# WattMeter_v4_SPI_Nov19_2018.net
KiCad netlist of a schematic drawn in EAGLE
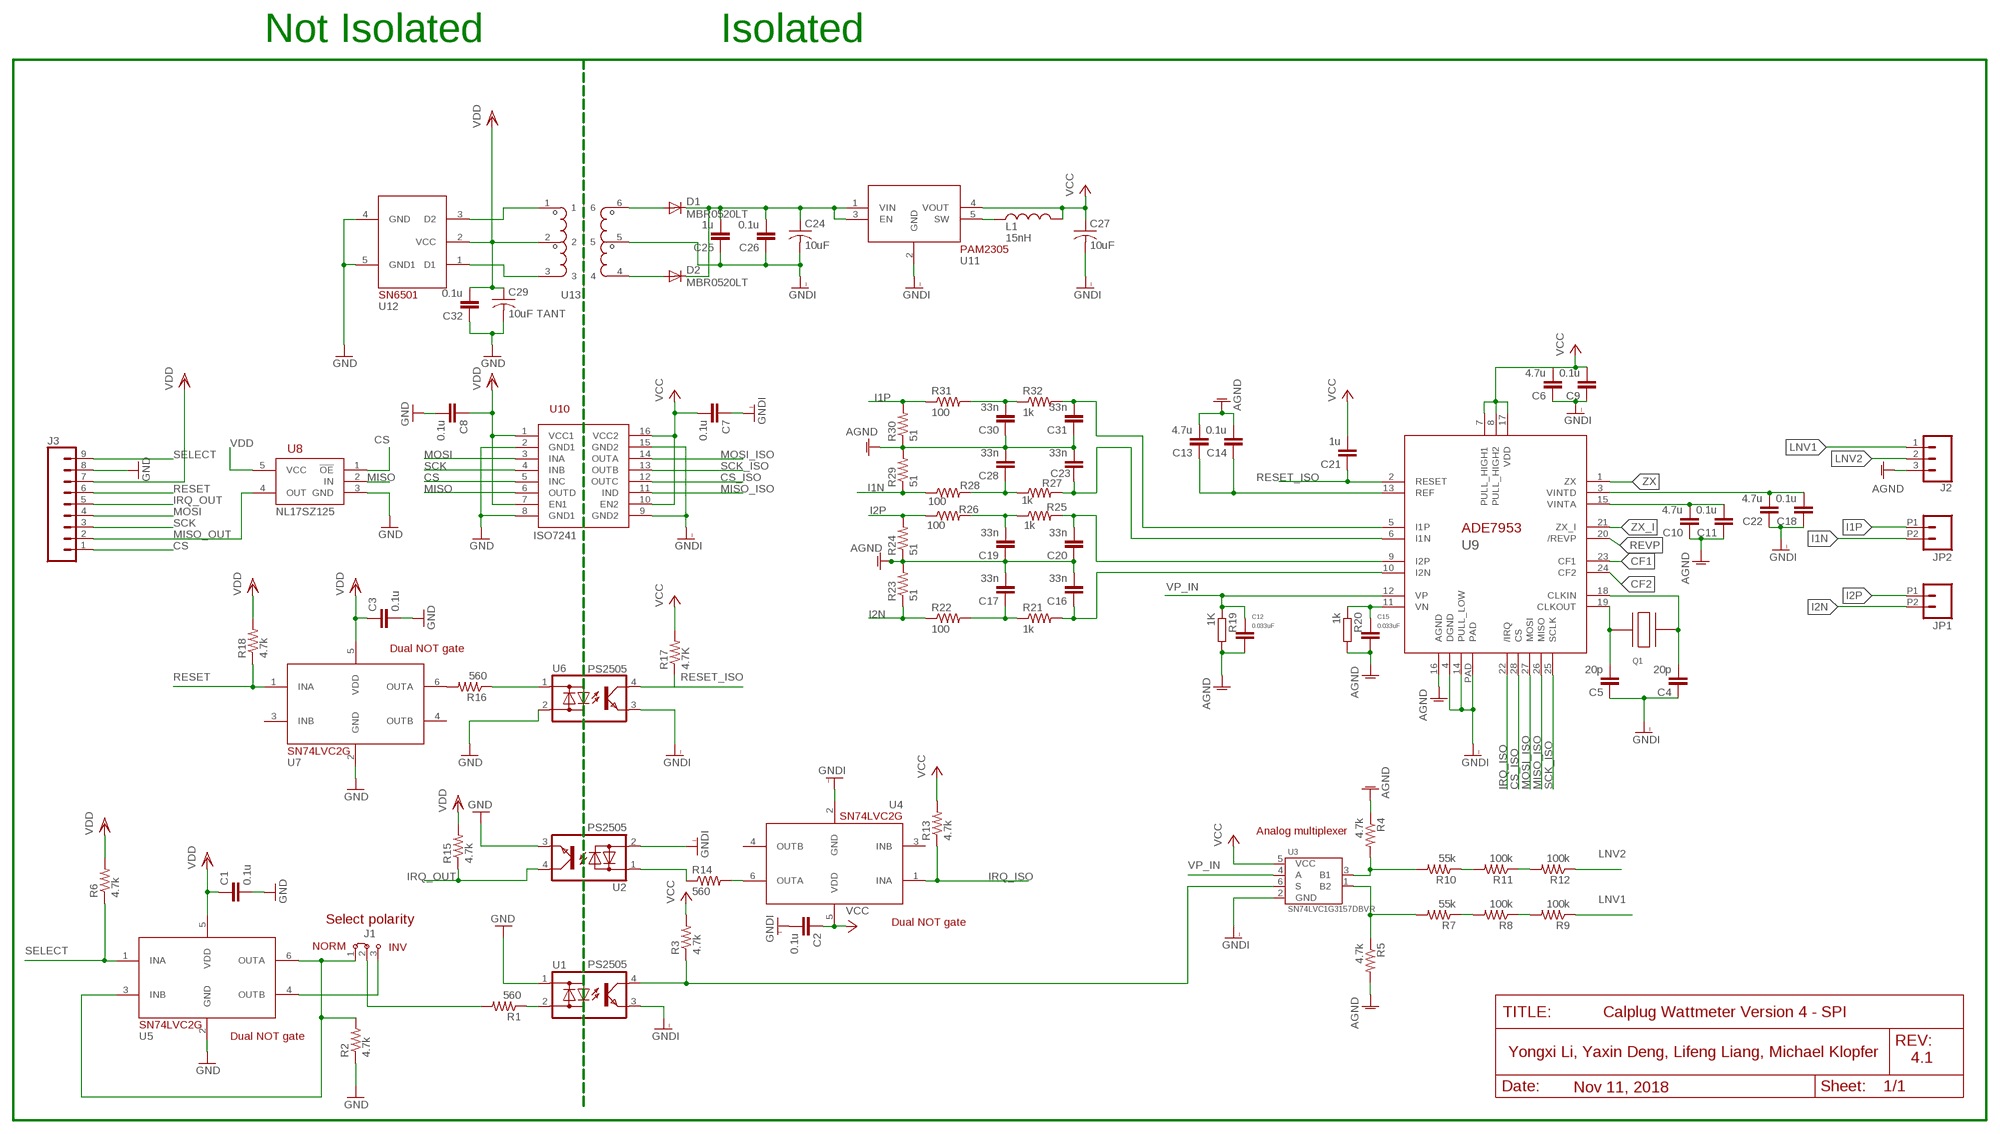
[diagram p0: schematic, sheet 1]

(export (version "E")
  (design (tool "Eeschema 10.0.6"))
  (components
    (comp (ref "C1")
      (value "0.1u")
      (footprint "eagle-import:0402-CAP")
      (libsource (lib "eagle-import") (part "0402-CAP"))
    )
    (comp (ref "C2")
      (value "0.1u")
      (footprint "eagle-import:0402-CAP")
      (libsource (lib "eagle-import") (part "0402-CAP"))
    )
    (comp (ref "C3")
      (value "0.1u")
      (footprint "eagle-import:0402-CAP")
      (libsource (lib "eagle-import") (part "0402-CAP"))
    )
    (comp (ref "C4")
      (value "20p")
      (footprint "eagle-import:0402-CAP")
      (libsource (lib "eagle-import") (part "0402-CAP"))
    )
    (comp (ref "C5")
      (value "20p")
      (footprint "eagle-import:0402-CAP")
      (libsource (lib "eagle-import") (part "0402-CAP"))
    )
    (comp (ref "C6")
      (value "4.7u")
      (footprint "eagle-import:0402-CAP")
      (libsource (lib "eagle-import") (part "0402-CAP"))
    )
    (comp (ref "C7")
      (value "0.1u")
      (footprint "eagle-import:0402-CAP")
      (libsource (lib "eagle-import") (part "0402-CAP"))
    )
    (comp (ref "C8")
      (value "0.1u")
      (footprint "eagle-import:0402-CAP")
      (libsource (lib "eagle-import") (part "0402-CAP"))
    )
    (comp (ref "C9")
      (value "0.1u")
      (footprint "eagle-import:0402-CAP")
      (libsource (lib "eagle-import") (part "0402-CAP"))
    )
    (comp (ref "C10")
      (value "4.7u")
      (footprint "eagle-import:0402-CAP")
      (libsource (lib "eagle-import") (part "0402-CAP"))
    )
    (comp (ref "C11")
      (value "0.1u")
      (footprint "eagle-import:0402-CAP")
      (libsource (lib "eagle-import") (part "0402-CAP"))
    )
    (comp (ref "C12")
      (value "0.033uF")
      (footprint "eagle-import:C0805K")
      (libsource (lib "eagle-import") (part "C-EUC0805K"))
    )
    (comp (ref "C13")
      (value "4.7u")
      (footprint "eagle-import:0402-CAP")
      (libsource (lib "eagle-import") (part "0402-CAP"))
    )
    (comp (ref "C14")
      (value "0.1u")
      (footprint "eagle-import:0402-CAP")
      (libsource (lib "eagle-import") (part "0402-CAP"))
    )
    (comp (ref "C15")
      (value "0.033uF")
      (footprint "eagle-import:C0805K")
      (libsource (lib "eagle-import") (part "C-EUC0805K"))
    )
    (comp (ref "C16")
      (value "33n")
      (footprint "eagle-import:0402-CAP")
      (libsource (lib "eagle-import") (part "0402-CAP"))
    )
    (comp (ref "C17")
      (value "33n")
      (footprint "eagle-import:0402-CAP")
      (libsource (lib "eagle-import") (part "0402-CAP"))
    )
    (comp (ref "C18")
      (value "0.1u")
      (footprint "eagle-import:0402-CAP")
      (libsource (lib "eagle-import") (part "0402-CAP"))
    )
    (comp (ref "C19")
      (value "33n")
      (footprint "eagle-import:0402-CAP")
      (libsource (lib "eagle-import") (part "0402-CAP"))
    )
    (comp (ref "C20")
      (value "33n")
      (footprint "eagle-import:0402-CAP")
      (libsource (lib "eagle-import") (part "0402-CAP"))
    )
    (comp (ref "C21")
      (value "1u")
      (footprint "eagle-import:0402-CAP")
      (libsource (lib "eagle-import") (part "0402-CAP"))
    )
    (comp (ref "C22")
      (value "4.7u")
      (footprint "eagle-import:0402-CAP")
      (libsource (lib "eagle-import") (part "0402-CAP"))
    )
    (comp (ref "C23")
      (value "33n")
      (footprint "eagle-import:0402-CAP")
      (libsource (lib "eagle-import") (part "0402-CAP"))
    )
    (comp (ref "C24")
      (value "10uF")
      (footprint "eagle-import:C0603")
      (libsource (lib "eagle-import") (part "C-USC0603"))
    )
    (comp (ref "C25")
      (value "1u")
      (footprint "eagle-import:0402-CAP")
      (libsource (lib "eagle-import") (part "0402-CAP"))
    )
    (comp (ref "C26")
      (value "0.1u")
      (footprint "eagle-import:0402-CAP")
      (libsource (lib "eagle-import") (part "0402-CAP"))
    )
    (comp (ref "C27")
      (value "10uF")
      (footprint "eagle-import:C0603")
      (libsource (lib "eagle-import") (part "C-USC0603"))
    )
    (comp (ref "C28")
      (value "33n")
      (footprint "eagle-import:0402-CAP")
      (libsource (lib "eagle-import") (part "0402-CAP"))
    )
    (comp (ref "C29")
      (value "10uF TANT")
      (footprint "eagle-import:C0603")
      (libsource (lib "eagle-import") (part "C-USC0603"))
    )
    (comp (ref "C30")
      (value "33n")
      (footprint "eagle-import:0402-CAP")
      (libsource (lib "eagle-import") (part "0402-CAP"))
    )
    (comp (ref "C31")
      (value "33n")
      (footprint "eagle-import:0402-CAP")
      (libsource (lib "eagle-import") (part "0402-CAP"))
    )
    (comp (ref "C32")
      (value "0.1u")
      (footprint "eagle-import:0402-CAP")
      (libsource (lib "eagle-import") (part "0402-CAP"))
    )
    (comp (ref "D1")
      (value "MBR0520LT")
      (footprint "eagle-import:SOD123")
      (libsource (lib "eagle-import") (part "MBR0520LT"))
    )
    (comp (ref "D2")
      (value "MBR0520LT")
      (footprint "eagle-import:SOD123")
      (libsource (lib "eagle-import") (part "MBR0520LT"))
    )
    (comp (ref "J1")
      (value "JUMPER3")
      (footprint "eagle-import:1X03")
      (libsource (lib "eagle-import") (part "JUMPER3"))
    )
    (comp (ref "J2")
      (value "CONN_03-SCREW-5MM")
      (footprint "eagle-import:SCREWTERMINAL-5MM-3")
      (libsource (lib "eagle-import") (part "CONN_03-SCREW-5MM"))
    )
    (comp (ref "J3")
      (value "CONN_09")
      (footprint "eagle-import:1X09")
      (libsource (lib "eagle-import") (part "CONN_09"))
    )
    (comp (ref "JP1")
      (value "M022.54MM_SCREWTERM")
      (footprint "eagle-import:1X02_2.54_SCREWTERM")
      (libsource (lib "eagle-import") (part "M022.54MM_SCREWTERM"))
    )
    (comp (ref "JP2")
      (value "M022.54MM_SCREWTERM")
      (footprint "eagle-import:1X02_2.54_SCREWTERM")
      (libsource (lib "eagle-import") (part "M022.54MM_SCREWTERM"))
    )
    (comp (ref "L1")
      (value "15nH")
      (footprint "eagle-import:0402-RES")
      (libsource (lib "eagle-import") (part "IND0402"))
    )
    (comp (ref "Q1")
      (value "QUARTZ_3.58M_2PIN")
      (footprint "eagle-import:HC-49S")
      (libsource (lib "eagle-import") (part "QUARTZ_3.58M_2PIN"))
    )
    (comp (ref "R1")
      (value "560")
      (footprint "eagle-import:0402-RES")
      (libsource (lib "eagle-import") (part "0402-RES"))
    )
    (comp (ref "R2")
      (value "4.7k")
      (footprint "eagle-import:0402-RES")
      (libsource (lib "eagle-import") (part "0402-RES"))
    )
    (comp (ref "R3")
      (value "4.7k")
      (footprint "eagle-import:0402-RES")
      (libsource (lib "eagle-import") (part "0402-RES"))
    )
    (comp (ref "R4")
      (value "4.7k")
      (footprint "eagle-import:0603-RES")
      (libsource (lib "eagle-import") (part "RESISTOR0603-RES"))
    )
    (comp (ref "R5")
      (value "4.7k")
      (footprint "eagle-import:0603-RES")
      (libsource (lib "eagle-import") (part "RESISTOR0603-RES"))
    )
    (comp (ref "R6")
      (value "4.7k")
      (footprint "eagle-import:0402-RES")
      (libsource (lib "eagle-import") (part "0402-RES"))
    )
    (comp (ref "R7")
      (value "55k")
      (footprint "eagle-import:0603-RES")
      (libsource (lib "eagle-import") (part "RESISTOR0603-RES"))
    )
    (comp (ref "R8")
      (value "100k")
      (footprint "eagle-import:0603-RES")
      (libsource (lib "eagle-import") (part "RESISTOR0603-RES"))
    )
    (comp (ref "R9")
      (value "100k")
      (footprint "eagle-import:0603-RES")
      (libsource (lib "eagle-import") (part "RESISTOR0603-RES"))
    )
    (comp (ref "R10")
      (value "55k")
      (footprint "eagle-import:0603-RES")
      (libsource (lib "eagle-import") (part "RESISTOR0603-RES"))
    )
    (comp (ref "R11")
      (value "100k")
      (footprint "eagle-import:0603-RES")
      (libsource (lib "eagle-import") (part "RESISTOR0603-RES"))
    )
    (comp (ref "R12")
      (value "100k")
      (footprint "eagle-import:0603-RES")
      (libsource (lib "eagle-import") (part "RESISTOR0603-RES"))
    )
    (comp (ref "R13")
      (value "4.7k")
      (footprint "eagle-import:0402-RES")
      (libsource (lib "eagle-import") (part "0402-RES"))
    )
    (comp (ref "R14")
      (value "560")
      (footprint "eagle-import:0402-RES")
      (libsource (lib "eagle-import") (part "0402-RES"))
    )
    (comp (ref "R15")
      (value "4.7k")
      (footprint "eagle-import:0402-RES")
      (libsource (lib "eagle-import") (part "0402-RES"))
    )
    (comp (ref "R16")
      (value "560")
      (footprint "eagle-import:0402-RES")
      (libsource (lib "eagle-import") (part "0402-RES"))
    )
    (comp (ref "R17")
      (value "4.7K")
      (footprint "eagle-import:0402-RES")
      (libsource (lib "eagle-import") (part "0402-RES"))
    )
    (comp (ref "R18")
      (value "4.7k")
      (footprint "eagle-import:0402-RES")
      (libsource (lib "eagle-import") (part "0402-RES"))
    )
    (comp (ref "R19")
      (value "1K")
      (footprint "eagle-import:C0805K@1")
      (libsource (lib "eagle-import") (part "R-EU_"))
    )
    (comp (ref "R20")
      (value "1k")
      (footprint "eagle-import:C0805K@1")
      (libsource (lib "eagle-import") (part "R-EU_"))
    )
    (comp (ref "R21")
      (value "1k")
      (footprint "eagle-import:0402-RES")
      (libsource (lib "eagle-import") (part "0402-RES"))
    )
    (comp (ref "R22")
      (value "100")
      (footprint "eagle-import:0402-RES")
      (libsource (lib "eagle-import") (part "0402-RES"))
    )
    (comp (ref "R23")
      (value "51")
      (footprint "eagle-import:0402-RES")
      (libsource (lib "eagle-import") (part "0402-RES"))
    )
    (comp (ref "R24")
      (value "51")
      (footprint "eagle-import:0402-RES")
      (libsource (lib "eagle-import") (part "0402-RES"))
    )
    (comp (ref "R25")
      (value "1k")
      (footprint "eagle-import:0402-RES")
      (libsource (lib "eagle-import") (part "0402-RES"))
    )
    (comp (ref "R26")
      (value "100")
      (footprint "eagle-import:0402-RES")
      (libsource (lib "eagle-import") (part "0402-RES"))
    )
    (comp (ref "R27")
      (value "1k")
      (footprint "eagle-import:0402-RES")
      (libsource (lib "eagle-import") (part "0402-RES"))
    )
    (comp (ref "R28")
      (value "100")
      (footprint "eagle-import:0402-RES")
      (libsource (lib "eagle-import") (part "0402-RES"))
    )
    (comp (ref "R29")
      (value "51")
      (footprint "eagle-import:0402-RES")
      (libsource (lib "eagle-import") (part "0402-RES"))
    )
    (comp (ref "R30")
      (value "51")
      (footprint "eagle-import:0402-RES")
      (libsource (lib "eagle-import") (part "0402-RES"))
    )
    (comp (ref "R31")
      (value "100")
      (footprint "eagle-import:0402-RES")
      (libsource (lib "eagle-import") (part "0402-RES"))
    )
    (comp (ref "R32")
      (value "1k")
      (footprint "eagle-import:0402-RES")
      (libsource (lib "eagle-import") (part "0402-RES"))
    )
    (comp (ref "U1")
      (value "PS2505")
      (footprint "eagle-import:PS2505")
      (libsource (lib "eagle-import") (part "PS2505"))
    )
    (comp (ref "U2")
      (value "PS2505")
      (footprint "eagle-import:PS2505")
      (libsource (lib "eagle-import") (part "PS2505"))
    )
    (comp (ref "U3")
      (value "SN74LVC1G3157DBVR")
      (footprint "eagle-import:SOT-23-6")
      (libsource (lib "eagle-import") (part "SN74LVC1G3157DBVR"))
    )
    (comp (ref "U4")
      (value "SN74LVC")
      (footprint "eagle-import:DCKT")
      (libsource (lib "eagle-import") (part "SN74LVC"))
    )
    (comp (ref "U5")
      (value "SN74LVC")
      (footprint "eagle-import:DCKT")
      (libsource (lib "eagle-import") (part "SN74LVC"))
    )
    (comp (ref "U6")
      (value "PS2505")
      (footprint "eagle-import:PS2505")
      (libsource (lib "eagle-import") (part "PS2505"))
    )
    (comp (ref "U7")
      (value "SN74LVC")
      (footprint "eagle-import:DCKT")
      (fields (field (name "SPICEPREFIX") "X"))
      (libsource (lib "eagle-import") (part "SN74LVC"))
    )
    (comp (ref "U8")
      (value "NL17SZ125")
      (footprint "eagle-import:NL17SZ125")
      (libsource (lib "eagle-import") (part "NL17SZ125"))
    )
    (comp (ref "U9")
      (value "ADE7953")
      (footprint "eagle-import:28-WFQFN")
      (libsource (lib "eagle-import") (part "ADE7953"))
    )
    (comp (ref "U10")
      (value "ISO7241")
      (footprint "eagle-import:16-SOIC")
      (libsource (lib "eagle-import") (part "ISO7241"))
    )
    (comp (ref "U11")
      (value "PAM2305")
      (footprint "eagle-import:TSOT25")
      (libsource (lib "eagle-import") (part "PAM2305"))
    )
    (comp (ref "U12")
      (value "SN6501")
      (footprint "eagle-import:SOT-23-5")
      (libsource (lib "eagle-import") (part "SN6501"))
    )
    (comp (ref "U13")
      (value "TRANSFO_3.3")
      (footprint "eagle-import:TRANSFO_3.3")
      (libsource (lib "eagle-import") (part "TRANSFO_3.3"))
    )
  )
  (nets
    (net (code "1") (name "/CS") (class "Default")
      (node (ref "J3") (pin "1") (pinfunction "1_1") (pintype "passive"))
      (node (ref "U10") (pin "5") (pinfunction "INC_5") (pintype "bidirectional"))
      (node (ref "U8") (pin "1") (pinfunction "~{OE}_1") (pintype "bidirectional"))
    )
    (net (code "2") (name "/CS_ISO") (class "Default")
      (node (ref "U10") (pin "12") (pinfunction "OUTC_12") (pintype "bidirectional"))
      (node (ref "U9") (pin "28") (pinfunction "CS_28") (pintype "bidirectional"))
    )
    (net (code "3") (name "/IRQ_ISO") (class "Default")
      (node (ref "R13") (pin "1") (pinfunction "1_1") (pintype "passive"))
      (node (ref "U4") (pin "1") (pinfunction "INA_1") (pintype "bidirectional"))
      (node (ref "U9") (pin "22") (pinfunction "/IRQ_22") (pintype "bidirectional"))
    )
    (net (code "4") (name "/IRQ_OUT") (class "Default")
      (node (ref "J3") (pin "5") (pinfunction "5_5") (pintype "passive"))
      (node (ref "R15") (pin "1") (pinfunction "1_1") (pintype "passive"))
      (node (ref "U2") (pin "4") (pinfunction "COLLERTOR_4") (pintype "passive"))
    )
    (net (code "5") (name "/MISO") (class "Default")
      (node (ref "U10") (pin "6") (pinfunction "OUTD_6") (pintype "bidirectional"))
      (node (ref "U8") (pin "2") (pinfunction "IN_2") (pintype "bidirectional"))
    )
    (net (code "6") (name "/MISO_ISO") (class "Default")
      (node (ref "U10") (pin "11") (pinfunction "IND_11") (pintype "bidirectional"))
      (node (ref "U9") (pin "26") (pinfunction "MISO_26") (pintype "bidirectional"))
    )
    (net (code "7") (name "/MISO_OUT") (class "Default")
      (node (ref "J3") (pin "2") (pinfunction "2_2") (pintype "passive"))
      (node (ref "U8") (pin "4") (pinfunction "OUT_4") (pintype "bidirectional"))
    )
    (net (code "8") (name "/MOSI") (class "Default")
      (node (ref "J3") (pin "4") (pinfunction "4_4") (pintype "passive"))
      (node (ref "U10") (pin "3") (pinfunction "INA_3") (pintype "bidirectional"))
    )
    (net (code "9") (name "/MOSI_ISO") (class "Default")
      (node (ref "U10") (pin "14") (pinfunction "OUTA_14") (pintype "bidirectional"))
      (node (ref "U9") (pin "27") (pinfunction "MOSI_27") (pintype "bidirectional"))
    )
    (net (code "10") (name "/RESET") (class "Default")
      (node (ref "J3") (pin "6") (pinfunction "6_6") (pintype "passive"))
      (node (ref "R18") (pin "1") (pinfunction "1_1") (pintype "passive"))
      (node (ref "U7") (pin "1") (pinfunction "INA_1") (pintype "bidirectional"))
    )
    (net (code "11") (name "/RESET_ISO") (class "Default")
      (node (ref "C21") (pin "1") (pinfunction "1_1") (pintype "passive"))
      (node (ref "R17") (pin "1") (pinfunction "1_1") (pintype "passive"))
      (node (ref "U6") (pin "4") (pinfunction "COLLERTOR_4") (pintype "passive"))
      (node (ref "U9") (pin "2") (pinfunction "RESET_2") (pintype "bidirectional"))
    )
    (net (code "12") (name "/SCK") (class "Default")
      (node (ref "J3") (pin "3") (pinfunction "3_3") (pintype "passive"))
      (node (ref "U10") (pin "4") (pinfunction "INB_4") (pintype "bidirectional"))
    )
    (net (code "13") (name "/SCK_ISO") (class "Default")
      (node (ref "U10") (pin "13") (pinfunction "OUTB_13") (pintype "bidirectional"))
      (node (ref "U9") (pin "25") (pinfunction "SCLK_25") (pintype "bidirectional"))
    )
    (net (code "14") (name "/SELECT") (class "Default")
      (node (ref "J3") (pin "9") (pinfunction "9_9") (pintype "passive"))
      (node (ref "R6") (pin "1") (pinfunction "1_1") (pintype "passive"))
      (node (ref "U5") (pin "1") (pinfunction "INA_1") (pintype "bidirectional"))
    )
    (net (code "15") (name "/VP_IN") (class "Default")
      (node (ref "C12") (pin "1") (pinfunction "1_1") (pintype "passive"))
      (node (ref "R19") (pin "1") (pinfunction "1_1") (pintype "passive"))
      (node (ref "U3") (pin "4") (pinfunction "A_4") (pintype "bidirectional"))
      (node (ref "U9") (pin "12") (pinfunction "VP_12") (pintype "bidirectional"))
    )
    (net (code "16") (name "AGND") (class "Default")
      (node (ref "C10") (pin "1") (pinfunction "1_1") (pintype "passive"))
      (node (ref "C11") (pin "1") (pinfunction "1_1") (pintype "passive"))
      (node (ref "C12") (pin "2") (pinfunction "2_2") (pintype "passive"))
      (node (ref "C13") (pin "2") (pinfunction "2_2") (pintype "passive"))
      (node (ref "C14") (pin "2") (pinfunction "2_2") (pintype "passive"))
      (node (ref "C15") (pin "2") (pinfunction "2_2") (pintype "passive"))
      (node (ref "C16") (pin "2") (pinfunction "2_2") (pintype "passive"))
      (node (ref "C17") (pin "2") (pinfunction "2_2") (pintype "passive"))
      (node (ref "C19") (pin "1") (pinfunction "1_1") (pintype "passive"))
      (node (ref "C20") (pin "1") (pinfunction "1_1") (pintype "passive"))
      (node (ref "C23") (pin "2") (pinfunction "2_2") (pintype "passive"))
      (node (ref "C28") (pin "2") (pinfunction "2_2") (pintype "passive"))
      (node (ref "C30") (pin "1") (pinfunction "1_1") (pintype "passive"))
      (node (ref "C31") (pin "1") (pinfunction "1_1") (pintype "passive"))
      (node (ref "J2") (pin "3") (pinfunction "3_3") (pintype "passive"))
      (node (ref "R19") (pin "2") (pinfunction "2_2") (pintype "passive"))
      (node (ref "R20") (pin "2") (pinfunction "2_2") (pintype "passive"))
      (node (ref "R23") (pin "2") (pinfunction "2_2") (pintype "passive"))
      (node (ref "R24") (pin "1") (pinfunction "1_1") (pintype "passive"))
      (node (ref "R29") (pin "2") (pinfunction "2_2") (pintype "passive"))
      (node (ref "R30") (pin "1") (pinfunction "1_1") (pintype "passive"))
      (node (ref "R4") (pin "1") (pinfunction "1_1") (pintype "passive"))
      (node (ref "R5") (pin "2") (pinfunction "2_2") (pintype "passive"))
      (node (ref "U9") (pin "16") (pinfunction "AGND_16") (pintype "bidirectional"))
    )
    (net (code "17") (name "CF1") (class "Default")
      (node (ref "U9") (pin "23") (pinfunction "CF1_23") (pintype "bidirectional"))
    )
    (net (code "18") (name "CF2") (class "Default")
      (node (ref "U9") (pin "24") (pinfunction "CF2_24") (pintype "bidirectional"))
    )
    (net (code "19") (name "GND") (class "Default")
      (node (ref "C1") (pin "2") (pinfunction "2_2") (pintype "passive"))
      (node (ref "C29") (pin "2") (pinfunction "2_2") (pintype "passive"))
      (node (ref "C3") (pin "2") (pinfunction "2_2") (pintype "passive"))
      (node (ref "C32") (pin "1") (pinfunction "1_1") (pintype "passive"))
      (node (ref "C8") (pin "2") (pinfunction "2_2") (pintype "passive"))
      (node (ref "J3") (pin "8") (pinfunction "8_8") (pintype "passive"))
      (node (ref "R2") (pin "1") (pinfunction "1_1") (pintype "passive"))
      (node (ref "U1") (pin "1") (pinfunction "ANODE_1") (pintype "passive"))
      (node (ref "U10") (pin "2") (pinfunction "GND1_2") (pintype "bidirectional"))
      (node (ref "U10") (pin "8") (pinfunction "GND1_8") (pintype "bidirectional"))
      (node (ref "U12") (pin "4") (pinfunction "GND_4") (pintype "bidirectional"))
      (node (ref "U12") (pin "5") (pinfunction "GND1_5") (pintype "bidirectional"))
      (node (ref "U2") (pin "3") (pinfunction "EMITTER_3") (pintype "passive"))
      (node (ref "U5") (pin "2") (pinfunction "GND_2") (pintype "bidirectional"))
      (node (ref "U6") (pin "2") (pinfunction "CATHODE_2") (pintype "passive"))
      (node (ref "U7") (pin "2") (pinfunction "GND_2") (pintype "bidirectional"))
      (node (ref "U8") (pin "3") (pinfunction "GND_3") (pintype "bidirectional"))
    )
    (net (code "20") (name "GNDI") (class "Default")
      (node (ref "C18") (pin "1") (pinfunction "1_1") (pintype "passive"))
      (node (ref "C2") (pin "2") (pinfunction "2_2") (pintype "passive"))
      (node (ref "C22") (pin "1") (pinfunction "1_1") (pintype "passive"))
      (node (ref "C24") (pin "2") (pinfunction "2_2") (pintype "passive"))
      (node (ref "C25") (pin "1") (pinfunction "1_1") (pintype "passive"))
      (node (ref "C26") (pin "1") (pinfunction "1_1") (pintype "passive"))
      (node (ref "C27") (pin "2") (pinfunction "2_2") (pintype "passive"))
      (node (ref "C4") (pin "1") (pinfunction "1_1") (pintype "passive"))
      (node (ref "C5") (pin "1") (pinfunction "1_1") (pintype "passive"))
      (node (ref "C6") (pin "1") (pinfunction "1_1") (pintype "passive"))
      (node (ref "C7") (pin "1") (pinfunction "1_1") (pintype "passive"))
      (node (ref "C9") (pin "1") (pinfunction "1_1") (pintype "passive"))
      (node (ref "U1") (pin "3") (pinfunction "EMITTER_3") (pintype "passive"))
      (node (ref "U10") (pin "15") (pinfunction "GND2_15") (pintype "bidirectional"))
      (node (ref "U10") (pin "9") (pinfunction "GND2_9") (pintype "bidirectional"))
      (node (ref "U11") (pin "2") (pinfunction "GND_2") (pintype "bidirectional"))
      (node (ref "U13") (pin "5") (pinfunction "5_5") (pintype "bidirectional"))
      (node (ref "U2") (pin "2") (pinfunction "CATHODE_2") (pintype "passive"))
      (node (ref "U3") (pin "2") (pinfunction "GND_2") (pintype "bidirectional"))
      (node (ref "U4") (pin "2") (pinfunction "GND_2") (pintype "bidirectional"))
      (node (ref "U6") (pin "3") (pinfunction "EMITTER_3") (pintype "passive"))
      (node (ref "U9") (pin "14") (pinfunction "PULL_LOW_14") (pintype "bidirectional"))
      (node (ref "U9") (pin "4") (pinfunction "DGND_4") (pintype "bidirectional"))
      (node (ref "U9") (pin "PAD") (pinfunction "PAD_PAD") (pintype "bidirectional"))
    )
    (net (code "21") (name "I1N") (class "Default")
      (node (ref "JP2") (pin "P2") (pinfunction "2_P2") (pintype "passive"))
      (node (ref "R28") (pin "1") (pinfunction "1_1") (pintype "passive"))
      (node (ref "R29") (pin "1") (pinfunction "1_1") (pintype "passive"))
    )
    (net (code "22") (name "I1P") (class "Default")
      (node (ref "JP2") (pin "P1") (pinfunction "1_P1") (pintype "passive"))
      (node (ref "R30") (pin "2") (pinfunction "2_2") (pintype "passive"))
      (node (ref "R31") (pin "1") (pinfunction "1_1") (pintype "passive"))
    )
    (net (code "23") (name "I2N") (class "Default")
      (node (ref "JP1") (pin "P2") (pinfunction "2_P2") (pintype "passive"))
      (node (ref "R22") (pin "1") (pinfunction "1_1") (pintype "passive"))
      (node (ref "R23") (pin "1") (pinfunction "1_1") (pintype "passive"))
    )
    (net (code "24") (name "I2P") (class "Default")
      (node (ref "JP1") (pin "P1") (pinfunction "1_P1") (pintype "passive"))
      (node (ref "R24") (pin "2") (pinfunction "2_2") (pintype "passive"))
      (node (ref "R26") (pin "1") (pinfunction "1_1") (pintype "passive"))
    )
    (net (code "25") (name "LNV1") (class "Default")
      (node (ref "J2") (pin "1") (pinfunction "1_1") (pintype "passive"))
      (node (ref "R9") (pin "1") (pinfunction "1_1") (pintype "passive"))
    )
    (net (code "26") (name "LNV2") (class "Default")
      (node (ref "J2") (pin "2") (pinfunction "2_2") (pintype "passive"))
      (node (ref "R12") (pin "1") (pinfunction "1_1") (pintype "passive"))
    )
    (net (code "27") (name "Net-(C17-Pad1)") (class "Default")
      (node (ref "C17") (pin "1") (pinfunction "1_1") (pintype "passive"))
      (node (ref "R21") (pin "1") (pinfunction "1_1") (pintype "passive"))
      (node (ref "R22") (pin "2") (pinfunction "2_2") (pintype "passive"))
    )
    (net (code "28") (name "Net-(C19-Pad2)") (class "Default")
      (node (ref "C19") (pin "2") (pinfunction "2_2") (pintype "passive"))
      (node (ref "R25") (pin "1") (pinfunction "1_1") (pintype "passive"))
      (node (ref "R26") (pin "2") (pinfunction "2_2") (pintype "passive"))
    )
    (net (code "29") (name "Net-(C28-Pad1)") (class "Default")
      (node (ref "C28") (pin "1") (pinfunction "1_1") (pintype "passive"))
      (node (ref "R27") (pin "1") (pinfunction "1_1") (pintype "passive"))
      (node (ref "R28") (pin "2") (pinfunction "2_2") (pintype "passive"))
    )
    (net (code "30") (name "Net-(C30-Pad2)") (class "Default")
      (node (ref "C30") (pin "2") (pinfunction "2_2") (pintype "passive"))
      (node (ref "R31") (pin "2") (pinfunction "2_2") (pintype "passive"))
      (node (ref "R32") (pin "1") (pinfunction "1_1") (pintype "passive"))
    )
    (net (code "31") (name "Net-(D1-PadA)") (class "Default")
      (node (ref "D1") (pin "A") (pinfunction "A_A") (pintype "passive"))
      (node (ref "U13") (pin "6") (pinfunction "6_6") (pintype "bidirectional"))
    )
    (net (code "32") (name "Net-(D2-PadA)") (class "Default")
      (node (ref "D2") (pin "A") (pinfunction "A_A") (pintype "passive"))
      (node (ref "U13") (pin "4") (pinfunction "4_4") (pintype "bidirectional"))
    )
    (net (code "33") (name "Net-(J1-Pad2)") (class "Default")
      (node (ref "J1") (pin "2") (pinfunction "2_2") (pintype "passive"))
      (node (ref "R1") (pin "2") (pinfunction "2_2") (pintype "passive"))
    )
    (net (code "34") (name "Net-(R7-Pad1)") (class "Default")
      (node (ref "R7") (pin "1") (pinfunction "1_1") (pintype "passive"))
      (node (ref "R8") (pin "2") (pinfunction "2_2") (pintype "passive"))
    )
    (net (code "35") (name "Net-(R8-Pad1)") (class "Default")
      (node (ref "R8") (pin "1") (pinfunction "1_1") (pintype "passive"))
      (node (ref "R9") (pin "2") (pinfunction "2_2") (pintype "passive"))
    )
    (net (code "36") (name "Net-(R10-Pad1)") (class "Default")
      (node (ref "R10") (pin "1") (pinfunction "1_1") (pintype "passive"))
      (node (ref "R11") (pin "2") (pinfunction "2_2") (pintype "passive"))
    )
    (net (code "37") (name "Net-(R11-Pad1)") (class "Default")
      (node (ref "R11") (pin "1") (pinfunction "1_1") (pintype "passive"))
      (node (ref "R12") (pin "2") (pinfunction "2_2") (pintype "passive"))
    )
    (net (code "38") (name "Net-(U1-CATHODE)") (class "Default")
      (node (ref "R1") (pin "1") (pinfunction "1_1") (pintype "passive"))
      (node (ref "U1") (pin "2") (pinfunction "CATHODE_2") (pintype "passive"))
    )
    (net (code "39") (name "Net-(U1-COLLERTOR)") (class "Default")
      (node (ref "R3") (pin "1") (pinfunction "1_1") (pintype "passive"))
      (node (ref "U1") (pin "4") (pinfunction "COLLERTOR_4") (pintype "passive"))
      (node (ref "U3") (pin "6") (pinfunction "S_6") (pintype "bidirectional"))
    )
    (net (code "40") (name "Net-(U2-ANODE)") (class "Default")
      (node (ref "R14") (pin "1") (pinfunction "1_1") (pintype "passive"))
      (node (ref "U2") (pin "1") (pinfunction "ANODE_1") (pintype "passive"))
    )
    (net (code "41") (name "Net-(U3-B1)") (class "Default")
      (node (ref "R10") (pin "2") (pinfunction "2_2") (pintype "passive"))
      (node (ref "R4") (pin "2") (pinfunction "2_2") (pintype "passive"))
      (node (ref "U3") (pin "3") (pinfunction "B1_3") (pintype "bidirectional"))
    )
    (net (code "42") (name "Net-(U3-B2)") (class "Default")
      (node (ref "R5") (pin "1") (pinfunction "1_1") (pintype "passive"))
      (node (ref "R7") (pin "2") (pinfunction "2_2") (pintype "passive"))
      (node (ref "U3") (pin "1") (pinfunction "B2_1") (pintype "bidirectional"))
    )
    (net (code "43") (name "Net-(U4-OUTA)") (class "Default")
      (node (ref "R14") (pin "2") (pinfunction "2_2") (pintype "passive"))
      (node (ref "U4") (pin "6") (pinfunction "OUTA_6") (pintype "bidirectional"))
    )
    (net (code "44") (name "Net-(U5-INB)") (class "Default")
      (node (ref "J1") (pin "1") (pinfunction "1_1") (pintype "passive"))
      (node (ref "R2") (pin "2") (pinfunction "2_2") (pintype "passive"))
      (node (ref "U5") (pin "3") (pinfunction "INB_3") (pintype "bidirectional"))
      (node (ref "U5") (pin "6") (pinfunction "OUTA_6") (pintype "bidirectional"))
    )
    (net (code "45") (name "Net-(U5-OUTB)") (class "Default")
      (node (ref "J1") (pin "3") (pinfunction "3_3") (pintype "passive"))
      (node (ref "U5") (pin "4") (pinfunction "OUTB_4") (pintype "bidirectional"))
    )
    (net (code "46") (name "Net-(U6-ANODE)") (class "Default")
      (node (ref "R16") (pin "1") (pinfunction "1_1") (pintype "passive"))
      (node (ref "U6") (pin "1") (pinfunction "ANODE_1") (pintype "passive"))
    )
    (net (code "47") (name "Net-(U7-OUTA)") (class "Default")
      (node (ref "R16") (pin "2") (pinfunction "2_2") (pintype "passive"))
      (node (ref "U7") (pin "6") (pinfunction "OUTA_6") (pintype "bidirectional"))
    )
    (net (code "48") (name "Net-(U9-CLKIN)") (class "Default")
      (node (ref "C4") (pin "2") (pinfunction "2_2") (pintype "passive"))
      (node (ref "Q1") (pin "2") (pinfunction "2_2") (pintype "bidirectional"))
      (node (ref "U9") (pin "18") (pinfunction "CLKIN_18") (pintype "bidirectional"))
    )
    (net (code "49") (name "Net-(U9-CLKOUT)") (class "Default")
      (node (ref "C5") (pin "2") (pinfunction "2_2") (pintype "passive"))
      (node (ref "Q1") (pin "1") (pinfunction "1_1") (pintype "bidirectional"))
      (node (ref "U9") (pin "19") (pinfunction "CLKOUT_19") (pintype "bidirectional"))
    )
    (net (code "50") (name "Net-(U9-I1N)") (class "Default")
      (node (ref "C23") (pin "1") (pinfunction "1_1") (pintype "passive"))
      (node (ref "R27") (pin "2") (pinfunction "2_2") (pintype "passive"))
      (node (ref "U9") (pin "6") (pinfunction "I1N_6") (pintype "bidirectional"))
    )
    (net (code "51") (name "Net-(U9-I1P)") (class "Default")
      (node (ref "C31") (pin "2") (pinfunction "2_2") (pintype "passive"))
      (node (ref "R32") (pin "2") (pinfunction "2_2") (pintype "passive"))
      (node (ref "U9") (pin "5") (pinfunction "I1P_5") (pintype "bidirectional"))
    )
    (net (code "52") (name "Net-(U9-I2N)") (class "Default")
      (node (ref "C16") (pin "1") (pinfunction "1_1") (pintype "passive"))
      (node (ref "R21") (pin "2") (pinfunction "2_2") (pintype "passive"))
      (node (ref "U9") (pin "10") (pinfunction "I2N_10") (pintype "bidirectional"))
    )
    (net (code "53") (name "Net-(U9-I2P)") (class "Default")
      (node (ref "C20") (pin "2") (pinfunction "2_2") (pintype "passive"))
      (node (ref "R25") (pin "2") (pinfunction "2_2") (pintype "passive"))
      (node (ref "U9") (pin "9") (pinfunction "I2P_9") (pintype "bidirectional"))
    )
    (net (code "54") (name "Net-(U9-REF)") (class "Default")
      (node (ref "C13") (pin "1") (pinfunction "1_1") (pintype "passive"))
      (node (ref "C14") (pin "1") (pinfunction "1_1") (pintype "passive"))
      (node (ref "U9") (pin "13") (pinfunction "REF_13") (pintype "bidirectional"))
    )
    (net (code "55") (name "Net-(U9-VINTA)") (class "Default")
      (node (ref "C10") (pin "2") (pinfunction "2_2") (pintype "passive"))
      (node (ref "C11") (pin "2") (pinfunction "2_2") (pintype "passive"))
      (node (ref "U9") (pin "15") (pinfunction "VINTA_15") (pintype "bidirectional"))
    )
    (net (code "56") (name "Net-(U9-VINTD)") (class "Default")
      (node (ref "C18") (pin "2") (pinfunction "2_2") (pintype "passive"))
      (node (ref "C22") (pin "2") (pinfunction "2_2") (pintype "passive"))
      (node (ref "U9") (pin "3") (pinfunction "VINTD_3") (pintype "bidirectional"))
    )
    (net (code "57") (name "Net-(U9-VN)") (class "Default")
      (node (ref "C15") (pin "1") (pinfunction "1_1") (pintype "passive"))
      (node (ref "R20") (pin "1") (pinfunction "1_1") (pintype "passive"))
      (node (ref "U9") (pin "11") (pinfunction "VN_11") (pintype "bidirectional"))
    )
    (net (code "58") (name "Net-(U11-EN)") (class "Default")
      (node (ref "C24") (pin "1") (pinfunction "1_1") (pintype "passive"))
      (node (ref "C25") (pin "2") (pinfunction "2_2") (pintype "passive"))
      (node (ref "C26") (pin "2") (pinfunction "2_2") (pintype "passive"))
      (node (ref "D1") (pin "C") (pinfunction "C_C") (pintype "passive"))
      (node (ref "D2") (pin "C") (pinfunction "C_C") (pintype "passive"))
      (node (ref "U11") (pin "1") (pinfunction "VIN_1") (pintype "bidirectional"))
      (node (ref "U11") (pin "3") (pinfunction "EN_3") (pintype "bidirectional"))
    )
    (net (code "59") (name "Net-(U11-SW)") (class "Default")
      (node (ref "L1") (pin "1") (pinfunction "1_1") (pintype "bidirectional"))
      (node (ref "U11") (pin "5") (pinfunction "SW_5") (pintype "bidirectional"))
    )
    (net (code "60") (name "Net-(U12-D1)") (class "Default")
      (node (ref "U12") (pin "1") (pinfunction "D1_1") (pintype "bidirectional"))
      (node (ref "U13") (pin "3") (pinfunction "3_3") (pintype "bidirectional"))
    )
    (net (code "61") (name "Net-(U12-D2)") (class "Default")
      (node (ref "U12") (pin "3") (pinfunction "D2_3") (pintype "bidirectional"))
      (node (ref "U13") (pin "1") (pinfunction "1_1") (pintype "bidirectional"))
    )
    (net (code "62") (name "REVP") (class "Default")
      (node (ref "U9") (pin "20") (pinfunction "/REVP_20") (pintype "bidirectional"))
    )
    (net (code "63") (name "VCC") (class "Default")
      (node (ref "C2") (pin "1") (pinfunction "1_1") (pintype "passive"))
      (node (ref "C21") (pin "2") (pinfunction "2_2") (pintype "passive"))
      (node (ref "C27") (pin "1") (pinfunction "1_1") (pintype "passive"))
      (node (ref "C6") (pin "2") (pinfunction "2_2") (pintype "passive"))
      (node (ref "C7") (pin "2") (pinfunction "2_2") (pintype "passive"))
      (node (ref "C9") (pin "2") (pinfunction "2_2") (pintype "passive"))
      (node (ref "L1") (pin "2") (pinfunction "2_2") (pintype "bidirectional"))
      (node (ref "R13") (pin "2") (pinfunction "2_2") (pintype "passive"))
      (node (ref "R17") (pin "2") (pinfunction "2_2") (pintype "passive"))
      (node (ref "R3") (pin "2") (pinfunction "2_2") (pintype "passive"))
      (node (ref "U10") (pin "10") (pinfunction "EN2_10") (pintype "bidirectional"))
      (node (ref "U10") (pin "16") (pinfunction "VCC2_16") (pintype "bidirectional"))
      (node (ref "U11") (pin "4") (pinfunction "VOUT_4") (pintype "bidirectional"))
      (node (ref "U3") (pin "5") (pinfunction "VCC_5") (pintype "bidirectional"))
      (node (ref "U4") (pin "5") (pinfunction "VDD_5") (pintype "bidirectional"))
      (node (ref "U9") (pin "17") (pinfunction "VDD_17") (pintype "bidirectional"))
      (node (ref "U9") (pin "7") (pinfunction "PULL_HIGH1_7") (pintype "bidirectional"))
      (node (ref "U9") (pin "8") (pinfunction "PULL_HIGH2_8") (pintype "bidirectional"))
    )
    (net (code "64") (name "VDD") (class "Default")
      (node (ref "C1") (pin "1") (pinfunction "1_1") (pintype "passive"))
      (node (ref "C29") (pin "1") (pinfunction "1_1") (pintype "passive"))
      (node (ref "C3") (pin "1") (pinfunction "1_1") (pintype "passive"))
      (node (ref "C32") (pin "2") (pinfunction "2_2") (pintype "passive"))
      (node (ref "C8") (pin "1") (pinfunction "1_1") (pintype "passive"))
      (node (ref "J3") (pin "7") (pinfunction "7_7") (pintype "passive"))
      (node (ref "R15") (pin "2") (pinfunction "2_2") (pintype "passive"))
      (node (ref "R18") (pin "2") (pinfunction "2_2") (pintype "passive"))
      (node (ref "R6") (pin "2") (pinfunction "2_2") (pintype "passive"))
      (node (ref "U10") (pin "1") (pinfunction "VCC1_1") (pintype "bidirectional"))
      (node (ref "U10") (pin "7") (pinfunction "EN1_7") (pintype "bidirectional"))
      (node (ref "U12") (pin "2") (pinfunction "VCC_2") (pintype "bidirectional"))
      (node (ref "U13") (pin "2") (pinfunction "2_2") (pintype "bidirectional"))
      (node (ref "U5") (pin "5") (pinfunction "VDD_5") (pintype "bidirectional"))
      (node (ref "U7") (pin "5") (pinfunction "VDD_5") (pintype "bidirectional"))
      (node (ref "U8") (pin "5") (pinfunction "VCC_5") (pintype "bidirectional"))
    )
    (net (code "65") (name "ZX") (class "Default")
      (node (ref "U9") (pin "1") (pinfunction "ZX_1") (pintype "bidirectional"))
    )
    (net (code "66") (name "ZX_I") (class "Default")
      (node (ref "U9") (pin "21") (pinfunction "ZX_I_21") (pintype "bidirectional"))
    )
    (net (code "67") (name "unconnected-(U4-INB-Pad3)") (class "Default")
      (node (ref "U4") (pin "3") (pinfunction "INB_3") (pintype "bidirectional"))
    )
    (net (code "68") (name "unconnected-(U4-OUTB-Pad4)") (class "Default")
      (node (ref "U4") (pin "4") (pinfunction "OUTB_4") (pintype "bidirectional"))
    )
    (net (code "69") (name "unconnected-(U7-INB-Pad3)") (class "Default")
      (node (ref "U7") (pin "3") (pinfunction "INB_3") (pintype "bidirectional"))
    )
    (net (code "70") (name "unconnected-(U7-OUTB-Pad4)") (class "Default")
      (node (ref "U7") (pin "4") (pinfunction "OUTB_4") (pintype "bidirectional"))
    )
  )
)
